# ProPrj_DRV8701.net
KiCad netlist of a schematic drawn in EasyEDA Pro
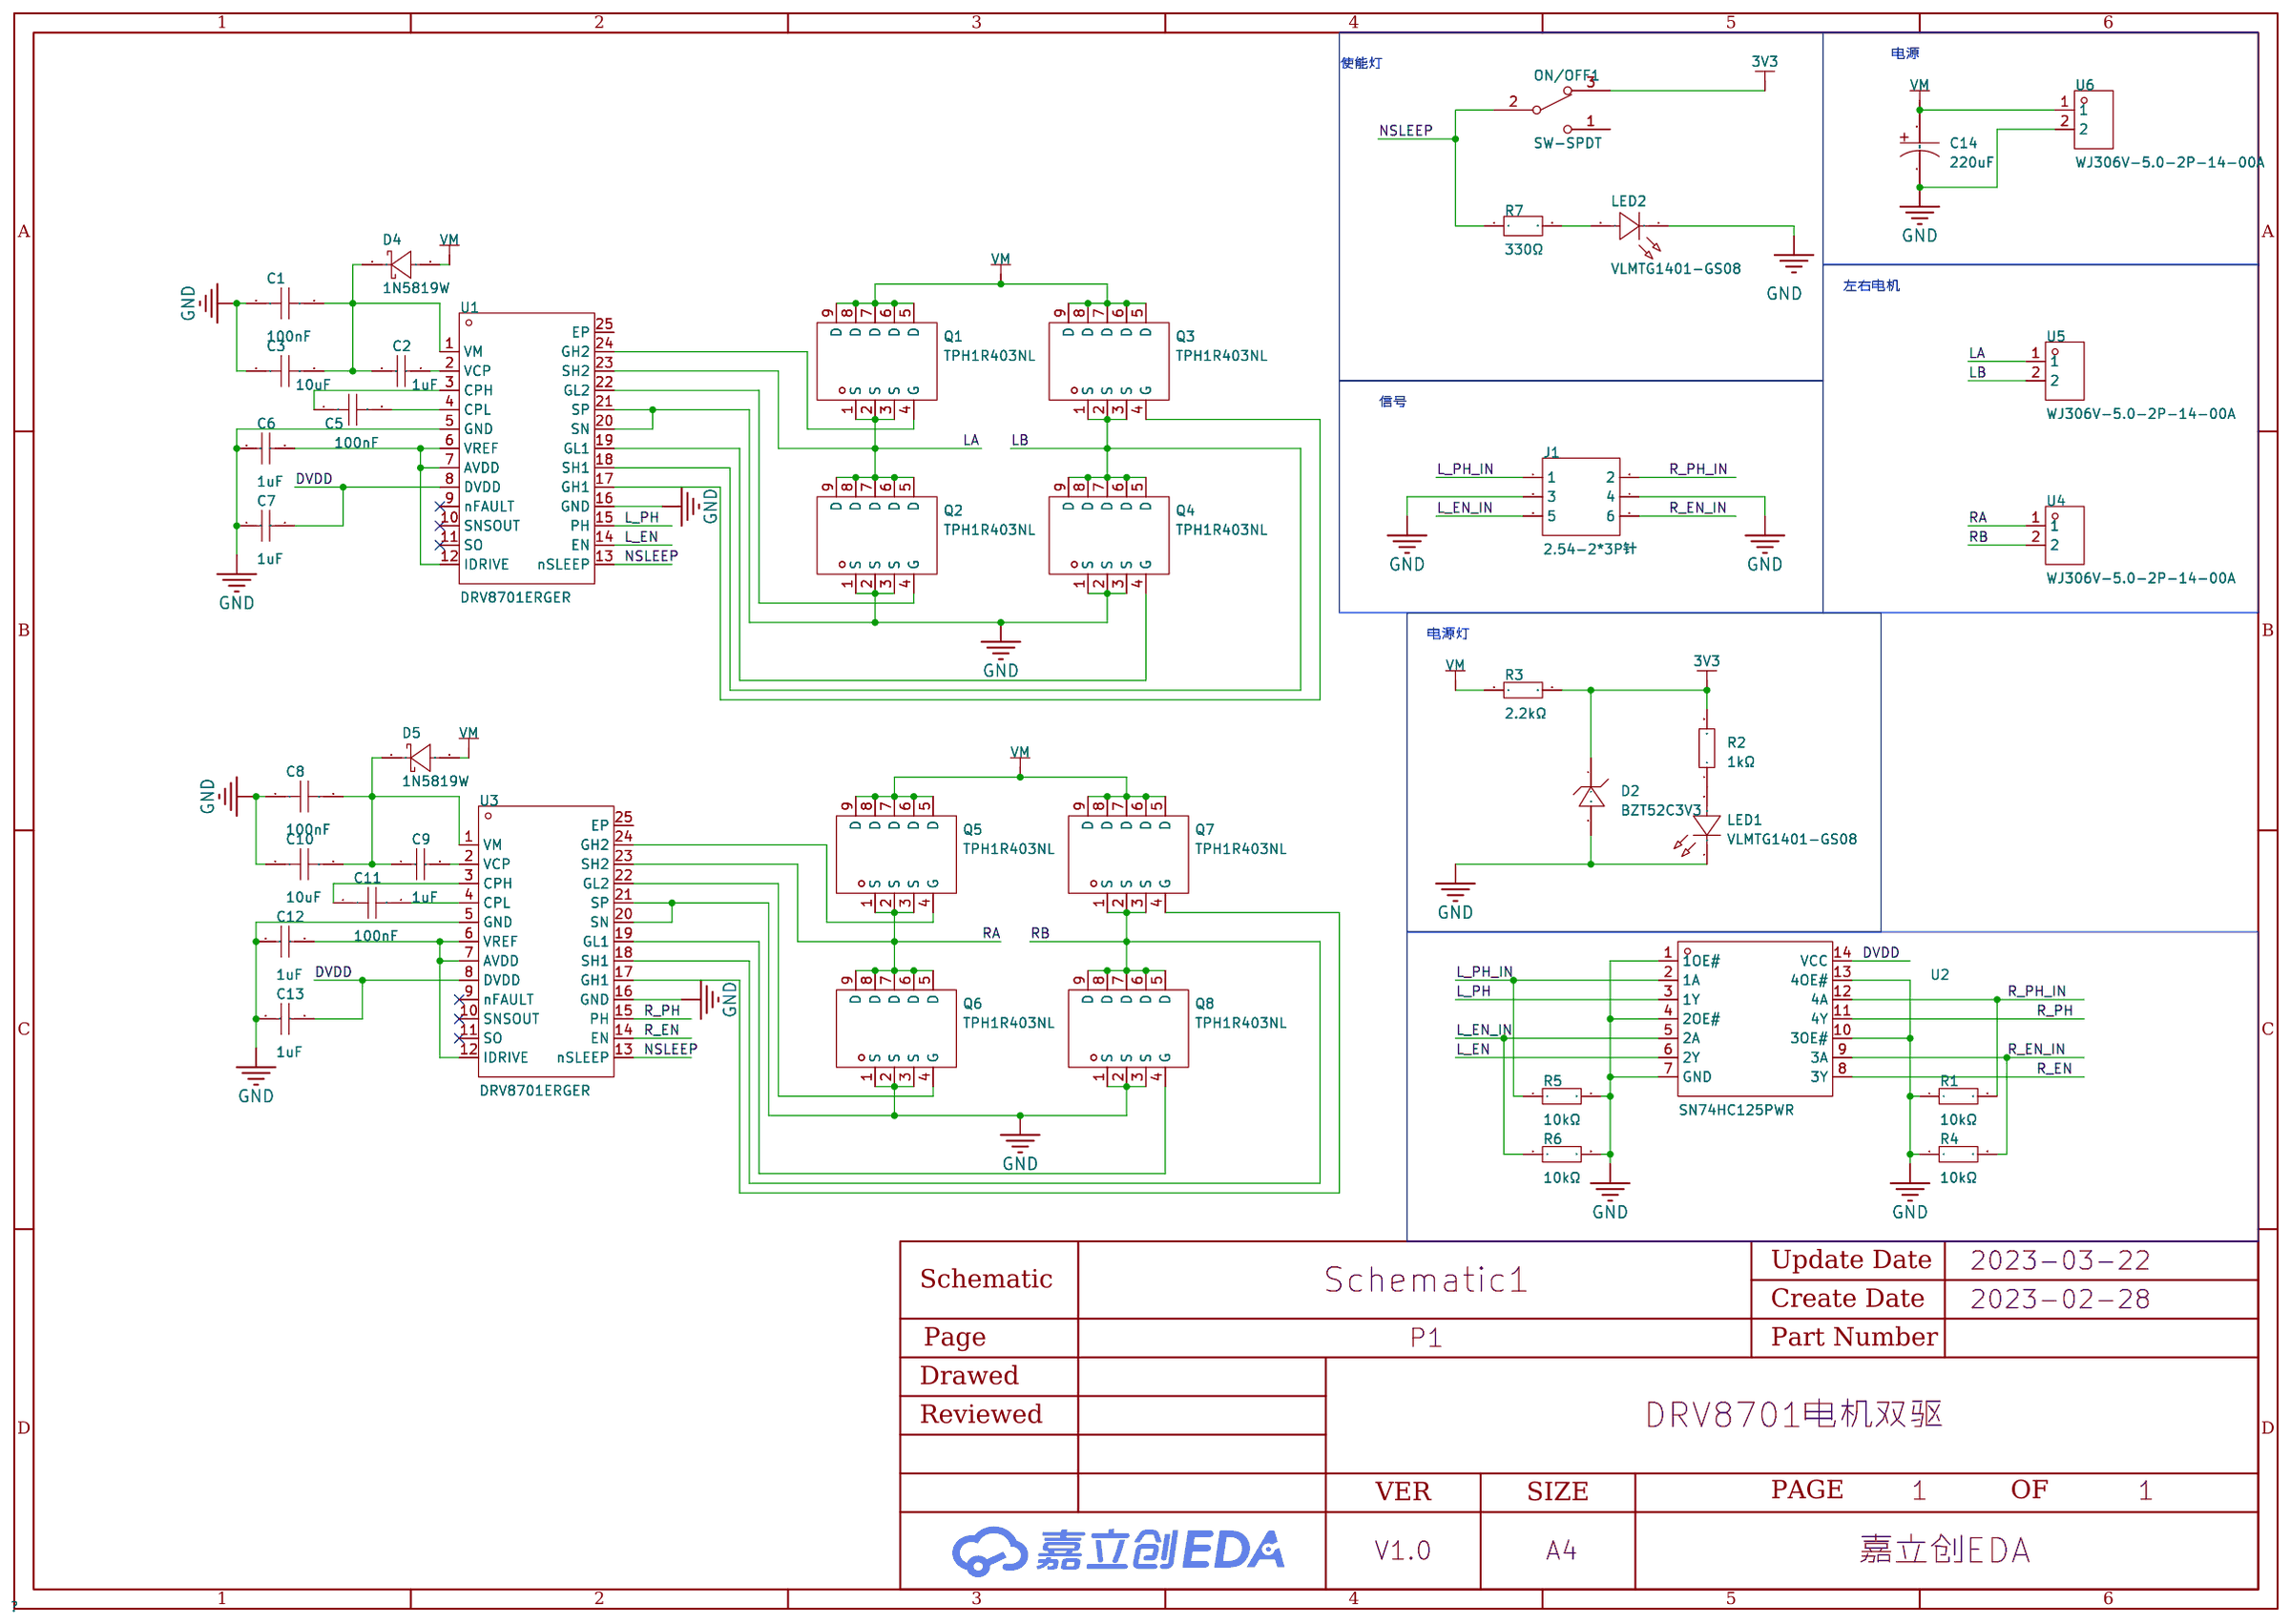
[diagram p0: schematic sheet]

(export (version "E")
  (design (tool "Eeschema 10.0.6"))
  (components
    (comp (ref "C1")
      (value "100nF")
      (footprint "easyedapro:C0603")
      (description "容值:100nF;精度:±10%;额定电压:50V;材质(温度系数):X7R;")
      (fields
        (field (name "Manufacturer Part") "CL10B104KB8NNNC")
        (field (name "Manufacturer") "SAMSUNG(三星)")
      )
      (libsource (lib "easyedapro") (part "CL10B104KB8NNNC"))
    )
    (comp (ref "C2")
      (value "1uF")
      (footprint "easyedapro:C0603")
      (description "容值:1uF;精度:±10%;额定电压:50V;材质(温度系数):X5R;")
      (fields
        (field (name "Manufacturer Part") "CL10A105KB8NNNC")
        (field (name "Manufacturer") "SAMSUNG(三星)")
      )
      (libsource (lib "easyedapro") (part "CL10A105KB8NNNC"))
    )
    (comp (ref "C3")
      (value "10uF")
      (footprint "easyedapro:C0805")
      (description "容值:10uF;精度:±10%;额定电压:50V;材质(温度系数):X5R;")
      (fields
        (field (name "Manufacturer Part") "CL21A106KBYQNNE")
        (field (name "Manufacturer") "SAMSUNG(三星)")
      )
      (libsource (lib "easyedapro") (part "CL21A106KBYQNNE"))
    )
    (comp (ref "C5")
      (value "100nF")
      (footprint "easyedapro:C0603")
      (description "容值:100nF;精度:±10%;额定电压:50V;材质(温度系数):X7R;")
      (fields
        (field (name "Manufacturer Part") "CL10B104KB8NNNC")
        (field (name "Manufacturer") "SAMSUNG(三星)")
      )
      (libsource (lib "easyedapro") (part "CL10B104KB8NNNC"))
    )
    (comp (ref "C6")
      (value "1uF")
      (footprint "easyedapro:C0603")
      (description "容值:1uF;精度:±10%;额定电压:50V;材质(温度系数):X5R;")
      (fields
        (field (name "Manufacturer Part") "CL10A105KB8NNNC")
        (field (name "Manufacturer") "SAMSUNG(三星)")
      )
      (libsource (lib "easyedapro") (part "CL10A105KB8NNNC"))
    )
    (comp (ref "C7")
      (value "1uF")
      (footprint "easyedapro:C0603")
      (description "容值:1uF;精度:±10%;额定电压:50V;材质(温度系数):X5R;")
      (fields
        (field (name "Manufacturer Part") "CL10A105KB8NNNC")
        (field (name "Manufacturer") "SAMSUNG(三星)")
      )
      (libsource (lib "easyedapro") (part "CL10A105KB8NNNC"))
    )
    (comp (ref "C8")
      (value "100nF")
      (footprint "easyedapro:C0603")
      (description "容值:100nF;精度:±10%;额定电压:50V;材质(温度系数):X7R;")
      (fields
        (field (name "Manufacturer Part") "CL10B104KB8NNNC")
        (field (name "Manufacturer") "SAMSUNG(三星)")
      )
      (libsource (lib "easyedapro") (part "CL10B104KB8NNNC"))
    )
    (comp (ref "C9")
      (value "1uF")
      (footprint "easyedapro:C0603")
      (description "容值:1uF;精度:±10%;额定电压:50V;材质(温度系数):X5R;")
      (fields
        (field (name "Manufacturer Part") "CL10A105KB8NNNC")
        (field (name "Manufacturer") "SAMSUNG(三星)")
      )
      (libsource (lib "easyedapro") (part "CL10A105KB8NNNC"))
    )
    (comp (ref "C10")
      (value "10uF")
      (footprint "easyedapro:C0805")
      (description "容值:10uF;精度:±10%;额定电压:50V;材质(温度系数):X5R;")
      (fields
        (field (name "Manufacturer Part") "CL21A106KBYQNNE")
        (field (name "Manufacturer") "SAMSUNG(三星)")
      )
      (libsource (lib "easyedapro") (part "CL21A106KBYQNNE"))
    )
    (comp (ref "C11")
      (value "100nF")
      (footprint "easyedapro:C0603")
      (description "容值:100nF;精度:±10%;额定电压:50V;材质(温度系数):X7R;")
      (fields
        (field (name "Manufacturer Part") "CL10B104KB8NNNC")
        (field (name "Manufacturer") "SAMSUNG(三星)")
      )
      (libsource (lib "easyedapro") (part "CL10B104KB8NNNC"))
    )
    (comp (ref "C12")
      (value "1uF")
      (footprint "easyedapro:C0603")
      (description "容值:1uF;精度:±10%;额定电压:50V;材质(温度系数):X5R;")
      (fields
        (field (name "Manufacturer Part") "CL10A105KB8NNNC")
        (field (name "Manufacturer") "SAMSUNG(三星)")
      )
      (libsource (lib "easyedapro") (part "CL10A105KB8NNNC"))
    )
    (comp (ref "C13")
      (value "1uF")
      (footprint "easyedapro:C0603")
      (description "容值:1uF;精度:±10%;额定电压:50V;材质(温度系数):X5R;")
      (fields
        (field (name "Manufacturer Part") "CL10A105KB8NNNC")
        (field (name "Manufacturer") "SAMSUNG(三星)")
      )
      (libsource (lib "easyedapro") (part "CL10A105KB8NNNC"))
    )
    (comp (ref "C14")
      (value "220uF")
      (footprint "easyedapro:CAP-SMD_BD8.0-L8.3-W8.3-FD")
      (fields (field (name "Manufacturer Part") "EEE1EA221UP") (field (name "Manufacturer") "PANASONIC(松下)"))
      (libsource (lib "easyedapro") (part "EEE1EA221UP"))
    )
    (comp (ref "D2")
      (value "BZT52C3V3")
      (footprint "easyedapro:SOD-123_L2.7-W1.6-LS3.7-RD-1")
      (description "二极管配置:-;稳压值(标称值):3.3V;稳压值(范围):3.3V~3.5V;功率:500mW;反向电流(Ir):5uA@1V;阻抗(Zzt):95Ω;")
      (fields (field (name "Manufacturer") "YONGYUTAI(永裕泰)"))
      (libsource (lib "easyedapro") (part "BZT52C3V3_C2891770"))
    )
    (comp (ref "D4")
      (value "1N5819W")
      (footprint "easyedapro:SOD-123_L2.7-W1.6-LS3.7-RD-1")
      (description "二极管配置:-;直流反向耐压(Vr):40V;平均整流电流(Io):1A;正向压降(Vf):900mV@3A;反向电流(Ir):1mA@40V;")
      (fields (field (name "Manufacturer") "TECH PUBLIC(台舟)"))
      (libsource (lib "easyedapro") (part "1N5819W_C2905650"))
    )
    (comp (ref "D5")
      (value "1N5819W")
      (footprint "easyedapro:SOD-123_L2.7-W1.6-LS3.7-RD-1")
      (description "二极管配置:-;直流反向耐压(Vr):40V;平均整流电流(Io):1A;正向压降(Vf):900mV@3A;反向电流(Ir):1mA@40V;")
      (fields (field (name "Manufacturer") "TECH PUBLIC(台舟)"))
      (libsource (lib "easyedapro") (part "1N5819W_C2905650"))
    )
    (comp (ref "J1")
      (value "2.54-2*3P针")
      (footprint "easyedapro:HDR-TH_6P-P2.54-V-M-R2-C3-S2.54-1")
      (fields (field (name "Manufacturer") "BOOMELE(博穆精密)"))
      (libsource (lib "easyedapro") (part "Header-Male-2.54_2x3"))
    )
    (comp (ref "LED1")
      (value "VLMTG1401-GS08")
      (footprint "easyedapro:LED0603-RD_GREEN")
      (description "照明颜色:-;色温 - CCT（K）:-;主波长/色坐标:-;正向电压（Vf）:-;")
      (fields (field (name "Manufacturer") "VISHAY(威世)"))
      (libsource (lib "easyedapro") (part "VLMTG1401-GS08"))
    )
    (comp (ref "LED2")
      (value "VLMTG1401-GS08")
      (footprint "easyedapro:LED0603-RD_GREEN")
      (description "照明颜色:-;色温 - CCT（K）:-;主波长/色坐标:-;正向电压（Vf）:-;")
      (fields (field (name "Manufacturer") "VISHAY(威世)"))
      (libsource (lib "easyedapro") (part "VLMTG1401-GS08"))
    )
    (comp (ref "ON/OFF1")
      (value "SW-SPDT")
      (footprint "easyedapro:SS12D10")
      (libsource (lib "easyedapro") (part "SW-SPDT"))
    )
    (comp (ref "Q1")
      (value "TPH1R403NL")
      (footprint "easyedapro:DSOP-8_L5.0-W5.0-P1.27-LS6.0-BL-EP")
      (fields (field (name "Manufacturer") "TOSHIBA(东芝)"))
      (libsource (lib "easyedapro") (part "TPH1R403NL"))
    )
    (comp (ref "Q2")
      (value "TPH1R403NL")
      (footprint "easyedapro:DSOP-8_L5.0-W5.0-P1.27-LS6.0-BL-EP")
      (fields (field (name "Manufacturer") "TOSHIBA(东芝)"))
      (libsource (lib "easyedapro") (part "TPH1R403NL"))
    )
    (comp (ref "Q3")
      (value "TPH1R403NL")
      (footprint "easyedapro:DSOP-8_L5.0-W5.0-P1.27-LS6.0-BL-EP")
      (fields (field (name "Manufacturer") "TOSHIBA(东芝)"))
      (libsource (lib "easyedapro") (part "TPH1R403NL"))
    )
    (comp (ref "Q4")
      (value "TPH1R403NL")
      (footprint "easyedapro:DSOP-8_L5.0-W5.0-P1.27-LS6.0-BL-EP")
      (fields (field (name "Manufacturer") "TOSHIBA(东芝)"))
      (libsource (lib "easyedapro") (part "TPH1R403NL"))
    )
    (comp (ref "Q5")
      (value "TPH1R403NL")
      (footprint "easyedapro:DSOP-8_L5.0-W5.0-P1.27-LS6.0-BL-EP")
      (fields (field (name "Manufacturer") "TOSHIBA(东芝)"))
      (libsource (lib "easyedapro") (part "TPH1R403NL"))
    )
    (comp (ref "Q6")
      (value "TPH1R403NL")
      (footprint "easyedapro:DSOP-8_L5.0-W5.0-P1.27-LS6.0-BL-EP")
      (fields (field (name "Manufacturer") "TOSHIBA(东芝)"))
      (libsource (lib "easyedapro") (part "TPH1R403NL"))
    )
    (comp (ref "Q7")
      (value "TPH1R403NL")
      (footprint "easyedapro:DSOP-8_L5.0-W5.0-P1.27-LS6.0-BL-EP")
      (fields (field (name "Manufacturer") "TOSHIBA(东芝)"))
      (libsource (lib "easyedapro") (part "TPH1R403NL"))
    )
    (comp (ref "Q8")
      (value "TPH1R403NL")
      (footprint "easyedapro:DSOP-8_L5.0-W5.0-P1.27-LS6.0-BL-EP")
      (fields (field (name "Manufacturer") "TOSHIBA(东芝)"))
      (libsource (lib "easyedapro") (part "TPH1R403NL"))
    )
    (comp (ref "R1")
      (value "10kΩ")
      (footprint "easyedapro:R0603")
      (description "电阻类型:厚膜电阻;阻值:10kΩ;精度:±1%;功率:100mW;温度系数:±100ppm/°C;最大工作电压:75V;工作温度范围:-55°C~+155°C;")
      (fields
        (field (name "Manufacturer Part") "0603WAF1002T5E")
        (field (name "Manufacturer") "UNI-ROYAL(厚声)")
      )
      (libsource (lib "easyedapro") (part "0603WAF1002T5E"))
    )
    (comp (ref "R2")
      (value "1kΩ")
      (footprint "easyedapro:R0603")
      (description "阻值:1kΩ;精度:±1%;功率:100mW;温度系数:±100ppm/°C;最大工作电压:75V;工作温度范围:-55°C~+155°C;")
      (fields (field (name "Manufacturer Part") "RC0603FR-071KL") (field (name "Manufacturer") "YAGEO(国巨)"))
      (libsource (lib "easyedapro") (part "RC0603FR-071KL"))
    )
    (comp (ref "R3")
      (value "2.2kΩ")
      (footprint "easyedapro:R0603")
      (description "电阻类型:薄膜电阻;阻值:2.2kΩ;精度:±0.1%;功率:100mW;温度系数:±25ppm/K;最大工作电压:75V;工作温度范围:-55°C~+155°C;")
      (fields (field (name "Manufacturer Part") "ERA3AEB222V") (field (name "Manufacturer") "PANASONIC(松下)"))
      (libsource (lib "easyedapro") (part "ERA3AEB222V"))
    )
    (comp (ref "R4")
      (value "10kΩ")
      (footprint "easyedapro:R0603")
      (description "电阻类型:厚膜电阻;阻值:10kΩ;精度:±1%;功率:100mW;温度系数:±100ppm/°C;最大工作电压:75V;工作温度范围:-55°C~+155°C;")
      (fields
        (field (name "Manufacturer Part") "0603WAF1002T5E")
        (field (name "Manufacturer") "UNI-ROYAL(厚声)")
      )
      (libsource (lib "easyedapro") (part "0603WAF1002T5E"))
    )
    (comp (ref "R5")
      (value "10kΩ")
      (footprint "easyedapro:R0603")
      (description "电阻类型:厚膜电阻;阻值:10kΩ;精度:±1%;功率:100mW;温度系数:±100ppm/°C;最大工作电压:75V;工作温度范围:-55°C~+155°C;")
      (fields
        (field (name "Manufacturer Part") "0603WAF1002T5E")
        (field (name "Manufacturer") "UNI-ROYAL(厚声)")
      )
      (libsource (lib "easyedapro") (part "0603WAF1002T5E"))
    )
    (comp (ref "R6")
      (value "10kΩ")
      (footprint "easyedapro:R0603")
      (description "电阻类型:厚膜电阻;阻值:10kΩ;精度:±1%;功率:100mW;温度系数:±100ppm/°C;最大工作电压:75V;工作温度范围:-55°C~+155°C;")
      (fields
        (field (name "Manufacturer Part") "0603WAF1002T5E")
        (field (name "Manufacturer") "UNI-ROYAL(厚声)")
      )
      (libsource (lib "easyedapro") (part "0603WAF1002T5E"))
    )
    (comp (ref "R7")
      (value "330Ω")
      (footprint "easyedapro:R0603")
      (description "电阻类型:厚膜电阻;阻值:330Ω;精度:±5%;功率:100mW;温度系数:±200ppm/°C;最大工作电压:-;工作温度范围:-55°C~+155°C;")
      (fields (field (name "Manufacturer Part") "ERJ3GEYJ331V") (field (name "Manufacturer") "PANASONIC(松下)"))
      (libsource (lib "easyedapro") (part "ERJ3GEYJ331V"))
    )
    (comp (ref "U1")
      (value "DRV8701ERGER")
      (footprint "easyedapro:VQFN-24_L4.0-W4.0-P0.50-BL-EP2.5")
      (description "DRV8701 DRV8701 H 桥栅极驱动器")
      (fields (field (name "Manufacturer") "TI(德州仪器)"))
      (libsource (lib "easyedapro") (part "DRV8701ERGER"))
    )
    (comp (ref "U2")
      (value "SN74HC125PWR")
      (footprint "easyedapro:TSSOP-14_L5.0-W4.4-P0.65-LS6.5-BL")
      (description "类型:缓冲器，非反相;电源电压:2V~6V;输入类型:-;输出类型:三态;低电平输出电流(IOL):7.8mA;高电平输出电流(IOH):7.8mA;工作温度:-40°C~+85°C;")
      (fields (field (name "Manufacturer") "TI(德州仪器)"))
      (libsource (lib "easyedapro") (part "SN74HC125PWR"))
    )
    (comp (ref "U3")
      (value "DRV8701ERGER")
      (footprint "easyedapro:VQFN-24_L4.0-W4.0-P0.50-BL-EP2.5")
      (description "DRV8701 DRV8701 H 桥栅极驱动器")
      (fields (field (name "Manufacturer") "TI(德州仪器)"))
      (libsource (lib "easyedapro") (part "DRV8701ERGER"))
    )
    (comp (ref "U4")
      (value "WJ306V-5.0-2P-14-00A")
      (footprint "easyedapro:CONN-TH_2P-P5.00_L7.6-W10.0")
      (fields (field (name "Manufacturer") "KANGNEX(康奈克斯电气)"))
      (libsource (lib "easyedapro") (part "WJ306V-5.0-2P-14-00A"))
    )
    (comp (ref "U5")
      (value "WJ306V-5.0-2P-14-00A")
      (footprint "easyedapro:CONN-TH_2P-P5.00_L7.6-W10.0")
      (fields (field (name "Manufacturer") "KANGNEX(康奈克斯电气)"))
      (libsource (lib "easyedapro") (part "WJ306V-5.0-2P-14-00A"))
    )
    (comp (ref "U6")
      (value "WJ306V-5.0-2P-14-00A")
      (footprint "easyedapro:CONN-TH_2P-P5.00_L7.6-W10.0")
      (fields (field (name "Manufacturer") "KANGNEX(康奈克斯电气)"))
      (libsource (lib "easyedapro") (part "WJ306V-5.0-2P-14-00A"))
    )
  )
  (nets
    (net (code "1") (name "/DVDD") (class "Default")
      (node (ref "C13") (pin "2") (pinfunction "2_2") (pintype "input"))
      (node (ref "C7") (pin "2") (pinfunction "2_2") (pintype "input"))
      (node (ref "U1") (pin "8") (pinfunction "DVDD_8") (pintype "input"))
      (node (ref "U2") (pin "14") (pinfunction "VCC_14") (pintype "input"))
      (node (ref "U3") (pin "8") (pinfunction "DVDD_8") (pintype "input"))
    )
    (net (code "2") (name "/LA") (class "Default")
      (node (ref "Q1") (pin "1") (pinfunction "S_1") (pintype "input"))
      (node (ref "Q1") (pin "2") (pinfunction "S_2") (pintype "input"))
      (node (ref "Q1") (pin "3") (pinfunction "S_3") (pintype "input"))
      (node (ref "Q2") (pin "5") (pinfunction "D_5") (pintype "input"))
      (node (ref "Q2") (pin "6") (pinfunction "D_6") (pintype "input"))
      (node (ref "Q2") (pin "7") (pinfunction "D_7") (pintype "input"))
      (node (ref "Q2") (pin "8") (pinfunction "D_8") (pintype "input"))
      (node (ref "Q2") (pin "9") (pinfunction "D_9") (pintype "input"))
      (node (ref "U1") (pin "23") (pinfunction "SH2_23") (pintype "input"))
      (node (ref "U5") (pin "1") (pinfunction "1_1") (pintype "input"))
    )
    (net (code "3") (name "/LB") (class "Default")
      (node (ref "Q3") (pin "1") (pinfunction "S_1") (pintype "input"))
      (node (ref "Q3") (pin "2") (pinfunction "S_2") (pintype "input"))
      (node (ref "Q3") (pin "3") (pinfunction "S_3") (pintype "input"))
      (node (ref "Q4") (pin "5") (pinfunction "D_5") (pintype "input"))
      (node (ref "Q4") (pin "6") (pinfunction "D_6") (pintype "input"))
      (node (ref "Q4") (pin "7") (pinfunction "D_7") (pintype "input"))
      (node (ref "Q4") (pin "8") (pinfunction "D_8") (pintype "input"))
      (node (ref "Q4") (pin "9") (pinfunction "D_9") (pintype "input"))
      (node (ref "U1") (pin "18") (pinfunction "SH1_18") (pintype "input"))
      (node (ref "U5") (pin "2") (pinfunction "2_2") (pintype "input"))
    )
    (net (code "4") (name "/L_EN") (class "Default")
      (node (ref "U1") (pin "14") (pinfunction "EN_14") (pintype "input"))
      (node (ref "U2") (pin "6") (pinfunction "2Y_6") (pintype "input"))
    )
    (net (code "5") (name "/L_EN_IN") (class "Default")
      (node (ref "J1") (pin "5") (pinfunction "5_5") (pintype "input"))
      (node (ref "R6") (pin "1") (pinfunction "1_1") (pintype "input"))
      (node (ref "U2") (pin "5") (pinfunction "2A_5") (pintype "input"))
    )
    (net (code "6") (name "/L_PH") (class "Default")
      (node (ref "U1") (pin "15") (pinfunction "PH_15") (pintype "input"))
      (node (ref "U2") (pin "3") (pinfunction "1Y_3") (pintype "input"))
    )
    (net (code "7") (name "/L_PH_IN") (class "Default")
      (node (ref "J1") (pin "1") (pinfunction "1_1") (pintype "input"))
      (node (ref "R5") (pin "1") (pinfunction "1_1") (pintype "input"))
      (node (ref "U2") (pin "2") (pinfunction "1A_2") (pintype "input"))
    )
    (net (code "8") (name "/NSLEEP") (class "Default")
      (node (ref "ON/OFF1") (pin "2") (pintype "input"))
      (node (ref "R7") (pin "1") (pinfunction "1_1") (pintype "input"))
      (node (ref "U1") (pin "13") (pinfunction "nSLEEP_13") (pintype "input"))
      (node (ref "U3") (pin "13") (pinfunction "nSLEEP_13") (pintype "input"))
    )
    (net (code "9") (name "/RA") (class "Default")
      (node (ref "Q5") (pin "1") (pinfunction "S_1") (pintype "input"))
      (node (ref "Q5") (pin "2") (pinfunction "S_2") (pintype "input"))
      (node (ref "Q5") (pin "3") (pinfunction "S_3") (pintype "input"))
      (node (ref "Q6") (pin "5") (pinfunction "D_5") (pintype "input"))
      (node (ref "Q6") (pin "6") (pinfunction "D_6") (pintype "input"))
      (node (ref "Q6") (pin "7") (pinfunction "D_7") (pintype "input"))
      (node (ref "Q6") (pin "8") (pinfunction "D_8") (pintype "input"))
      (node (ref "Q6") (pin "9") (pinfunction "D_9") (pintype "input"))
      (node (ref "U3") (pin "23") (pinfunction "SH2_23") (pintype "input"))
      (node (ref "U4") (pin "1") (pinfunction "1_1") (pintype "input"))
    )
    (net (code "10") (name "/RB") (class "Default")
      (node (ref "Q7") (pin "1") (pinfunction "S_1") (pintype "input"))
      (node (ref "Q7") (pin "2") (pinfunction "S_2") (pintype "input"))
      (node (ref "Q7") (pin "3") (pinfunction "S_3") (pintype "input"))
      (node (ref "Q8") (pin "5") (pinfunction "D_5") (pintype "input"))
      (node (ref "Q8") (pin "6") (pinfunction "D_6") (pintype "input"))
      (node (ref "Q8") (pin "7") (pinfunction "D_7") (pintype "input"))
      (node (ref "Q8") (pin "8") (pinfunction "D_8") (pintype "input"))
      (node (ref "Q8") (pin "9") (pinfunction "D_9") (pintype "input"))
      (node (ref "U3") (pin "18") (pinfunction "SH1_18") (pintype "input"))
      (node (ref "U4") (pin "2") (pinfunction "2_2") (pintype "input"))
    )
    (net (code "11") (name "/R_EN") (class "Default")
      (node (ref "U2") (pin "8") (pinfunction "3Y_8") (pintype "input"))
      (node (ref "U3") (pin "14") (pinfunction "EN_14") (pintype "input"))
    )
    (net (code "12") (name "/R_EN_IN") (class "Default")
      (node (ref "J1") (pin "6") (pinfunction "6_6") (pintype "input"))
      (node (ref "R4") (pin "2") (pinfunction "2_2") (pintype "input"))
      (node (ref "U2") (pin "9") (pinfunction "3A_9") (pintype "input"))
    )
    (net (code "13") (name "/R_PH") (class "Default")
      (node (ref "U2") (pin "11") (pinfunction "4Y_11") (pintype "input"))
      (node (ref "U3") (pin "15") (pinfunction "PH_15") (pintype "input"))
    )
    (net (code "14") (name "/R_PH_IN") (class "Default")
      (node (ref "J1") (pin "2") (pinfunction "2_2") (pintype "input"))
      (node (ref "R1") (pin "2") (pinfunction "2_2") (pintype "input"))
      (node (ref "U2") (pin "12") (pinfunction "4A_12") (pintype "input"))
    )
    (net (code "15") (name "3V3") (class "Default")
      (node (ref "D2") (pin "1") (pinfunction "1_1") (pintype "input"))
      (node (ref "ON/OFF1") (pin "3") (pintype "input"))
      (node (ref "R2") (pin "2") (pinfunction "2_2") (pintype "input"))
      (node (ref "R3") (pin "2") (pinfunction "2_2") (pintype "input"))
    )
    (net (code "16") (name "GND") (class "Default")
      (node (ref "C1") (pin "1") (pinfunction "1_1") (pintype "input"))
      (node (ref "C10") (pin "1") (pinfunction "1_1") (pintype "input"))
      (node (ref "C12") (pin "1") (pinfunction "1_1") (pintype "input"))
      (node (ref "C13") (pin "1") (pinfunction "1_1") (pintype "input"))
      (node (ref "C14") (pin "2") (pinfunction "2_2") (pintype "input"))
      (node (ref "C3") (pin "1") (pinfunction "1_1") (pintype "input"))
      (node (ref "C6") (pin "1") (pinfunction "1_1") (pintype "input"))
      (node (ref "C7") (pin "1") (pinfunction "1_1") (pintype "input"))
      (node (ref "C8") (pin "1") (pinfunction "1_1") (pintype "input"))
      (node (ref "D2") (pin "2") (pinfunction "2_2") (pintype "input"))
      (node (ref "J1") (pin "3") (pinfunction "3_3") (pintype "input"))
      (node (ref "J1") (pin "4") (pinfunction "4_4") (pintype "input"))
      (node (ref "LED1") (pin "1") (pinfunction "K_1") (pintype "input"))
      (node (ref "LED2") (pin "1") (pinfunction "K_1") (pintype "input"))
      (node (ref "Q2") (pin "1") (pinfunction "S_1") (pintype "input"))
      (node (ref "Q2") (pin "2") (pinfunction "S_2") (pintype "input"))
      (node (ref "Q2") (pin "3") (pinfunction "S_3") (pintype "input"))
      (node (ref "Q4") (pin "1") (pinfunction "S_1") (pintype "input"))
      (node (ref "Q4") (pin "2") (pinfunction "S_2") (pintype "input"))
      (node (ref "Q4") (pin "3") (pinfunction "S_3") (pintype "input"))
      (node (ref "Q6") (pin "1") (pinfunction "S_1") (pintype "input"))
      (node (ref "Q6") (pin "2") (pinfunction "S_2") (pintype "input"))
      (node (ref "Q6") (pin "3") (pinfunction "S_3") (pintype "input"))
      (node (ref "Q8") (pin "1") (pinfunction "S_1") (pintype "input"))
      (node (ref "Q8") (pin "2") (pinfunction "S_2") (pintype "input"))
      (node (ref "Q8") (pin "3") (pinfunction "S_3") (pintype "input"))
      (node (ref "R1") (pin "1") (pinfunction "1_1") (pintype "input"))
      (node (ref "R4") (pin "1") (pinfunction "1_1") (pintype "input"))
      (node (ref "R5") (pin "2") (pinfunction "2_2") (pintype "input"))
      (node (ref "R6") (pin "2") (pinfunction "2_2") (pintype "input"))
      (node (ref "U1") (pin "16") (pinfunction "GND_16") (pintype "input"))
      (node (ref "U1") (pin "20") (pinfunction "SN_20") (pintype "input"))
      (node (ref "U1") (pin "21") (pinfunction "SP_21") (pintype "input"))
      (node (ref "U1") (pin "5") (pinfunction "GND_5") (pintype "input"))
      (node (ref "U2") (pin "1") (pinfunction "1OE#_1") (pintype "input"))
      (node (ref "U2") (pin "10") (pinfunction "3OE#_10") (pintype "input"))
      (node (ref "U2") (pin "13") (pinfunction "4OE#_13") (pintype "input"))
      (node (ref "U2") (pin "4") (pinfunction "2OE#_4") (pintype "input"))
      (node (ref "U2") (pin "7") (pinfunction "GND_7") (pintype "input"))
      (node (ref "U3") (pin "16") (pinfunction "GND_16") (pintype "input"))
      (node (ref "U3") (pin "20") (pinfunction "SN_20") (pintype "input"))
      (node (ref "U3") (pin "21") (pinfunction "SP_21") (pintype "input"))
      (node (ref "U3") (pin "5") (pinfunction "GND_5") (pintype "input"))
      (node (ref "U6") (pin "2") (pinfunction "2_2") (pintype "input"))
    )
    (net (code "17") (name "Net-(D4-K)") (class "Default")
      (node (ref "C1") (pin "2") (pinfunction "2_2") (pintype "input"))
      (node (ref "C2") (pin "1") (pinfunction "1_1") (pintype "input"))
      (node (ref "C3") (pin "2") (pinfunction "2_2") (pintype "input"))
      (node (ref "D4") (pin "1") (pinfunction "K_1") (pintype "input"))
      (node (ref "U1") (pin "1") (pinfunction "VM_1") (pintype "input"))
    )
    (net (code "18") (name "Net-(D5-K)") (class "Default")
      (node (ref "C10") (pin "2") (pinfunction "2_2") (pintype "input"))
      (node (ref "C8") (pin "2") (pinfunction "2_2") (pintype "input"))
      (node (ref "C9") (pin "1") (pinfunction "1_1") (pintype "input"))
      (node (ref "D5") (pin "1") (pinfunction "K_1") (pintype "input"))
      (node (ref "U3") (pin "1") (pinfunction "VM_1") (pintype "input"))
    )
    (net (code "19") (name "Net-(LED1-A)") (class "Default")
      (node (ref "LED1") (pin "2") (pinfunction "A_2") (pintype "input"))
      (node (ref "R2") (pin "1") (pinfunction "1_1") (pintype "input"))
    )
    (net (code "20") (name "Net-(LED2-A)") (class "Default")
      (node (ref "LED2") (pin "2") (pinfunction "A_2") (pintype "input"))
      (node (ref "R7") (pin "2") (pinfunction "2_2") (pintype "input"))
    )
    (net (code "21") (name "Net-(Q1-G)") (class "Default")
      (node (ref "Q1") (pin "4") (pinfunction "G_4") (pintype "input"))
      (node (ref "U1") (pin "24") (pinfunction "GH2_24") (pintype "input"))
    )
    (net (code "22") (name "Net-(Q2-G)") (class "Default")
      (node (ref "Q2") (pin "4") (pinfunction "G_4") (pintype "input"))
      (node (ref "U1") (pin "22") (pinfunction "GL2_22") (pintype "input"))
    )
    (net (code "23") (name "Net-(Q3-G)") (class "Default")
      (node (ref "Q3") (pin "4") (pinfunction "G_4") (pintype "input"))
      (node (ref "U1") (pin "17") (pinfunction "GH1_17") (pintype "input"))
    )
    (net (code "24") (name "Net-(Q4-G)") (class "Default")
      (node (ref "Q4") (pin "4") (pinfunction "G_4") (pintype "input"))
      (node (ref "U1") (pin "19") (pinfunction "GL1_19") (pintype "input"))
    )
    (net (code "25") (name "Net-(Q5-G)") (class "Default")
      (node (ref "Q5") (pin "4") (pinfunction "G_4") (pintype "input"))
      (node (ref "U3") (pin "24") (pinfunction "GH2_24") (pintype "input"))
    )
    (net (code "26") (name "Net-(Q6-G)") (class "Default")
      (node (ref "Q6") (pin "4") (pinfunction "G_4") (pintype "input"))
      (node (ref "U3") (pin "22") (pinfunction "GL2_22") (pintype "input"))
    )
    (net (code "27") (name "Net-(Q7-G)") (class "Default")
      (node (ref "Q7") (pin "4") (pinfunction "G_4") (pintype "input"))
      (node (ref "U3") (pin "17") (pinfunction "GH1_17") (pintype "input"))
    )
    (net (code "28") (name "Net-(Q8-G)") (class "Default")
      (node (ref "Q8") (pin "4") (pinfunction "G_4") (pintype "input"))
      (node (ref "U3") (pin "19") (pinfunction "GL1_19") (pintype "input"))
    )
    (net (code "29") (name "Net-(U1-AVDD)") (class "Default")
      (node (ref "C6") (pin "2") (pinfunction "2_2") (pintype "input"))
      (node (ref "U1") (pin "12") (pinfunction "IDRIVE_12") (pintype "input"))
      (node (ref "U1") (pin "6") (pinfunction "VREF_6") (pintype "input"))
      (node (ref "U1") (pin "7") (pinfunction "AVDD_7") (pintype "input"))
    )
    (net (code "30") (name "Net-(U1-CPH)") (class "Default")
      (node (ref "C5") (pin "1") (pinfunction "1_1") (pintype "input"))
      (node (ref "U1") (pin "3") (pinfunction "CPH_3") (pintype "input"))
    )
    (net (code "31") (name "Net-(U1-CPL)") (class "Default")
      (node (ref "C5") (pin "2") (pinfunction "2_2") (pintype "input"))
      (node (ref "U1") (pin "4") (pinfunction "CPL_4") (pintype "input"))
    )
    (net (code "32") (name "Net-(U1-VCP)") (class "Default")
      (node (ref "C2") (pin "2") (pinfunction "2_2") (pintype "input"))
      (node (ref "U1") (pin "2") (pinfunction "VCP_2") (pintype "input"))
    )
    (net (code "33") (name "Net-(U3-AVDD)") (class "Default")
      (node (ref "C12") (pin "2") (pinfunction "2_2") (pintype "input"))
      (node (ref "U3") (pin "12") (pinfunction "IDRIVE_12") (pintype "input"))
      (node (ref "U3") (pin "6") (pinfunction "VREF_6") (pintype "input"))
      (node (ref "U3") (pin "7") (pinfunction "AVDD_7") (pintype "input"))
    )
    (net (code "34") (name "Net-(U3-CPH)") (class "Default")
      (node (ref "C11") (pin "1") (pinfunction "1_1") (pintype "input"))
      (node (ref "U3") (pin "3") (pinfunction "CPH_3") (pintype "input"))
    )
    (net (code "35") (name "Net-(U3-CPL)") (class "Default")
      (node (ref "C11") (pin "2") (pinfunction "2_2") (pintype "input"))
      (node (ref "U3") (pin "4") (pinfunction "CPL_4") (pintype "input"))
    )
    (net (code "36") (name "Net-(U3-VCP)") (class "Default")
      (node (ref "C9") (pin "2") (pinfunction "2_2") (pintype "input"))
      (node (ref "U3") (pin "2") (pinfunction "VCP_2") (pintype "input"))
    )
    (net (code "37") (name "VM") (class "Default")
      (node (ref "C14") (pin "1") (pinfunction "1_1") (pintype "input"))
      (node (ref "D4") (pin "2") (pinfunction "A_2") (pintype "input"))
      (node (ref "D5") (pin "2") (pinfunction "A_2") (pintype "input"))
      (node (ref "Q1") (pin "5") (pinfunction "D_5") (pintype "input"))
      (node (ref "Q1") (pin "6") (pinfunction "D_6") (pintype "input"))
      (node (ref "Q1") (pin "7") (pinfunction "D_7") (pintype "input"))
      (node (ref "Q1") (pin "8") (pinfunction "D_8") (pintype "input"))
      (node (ref "Q1") (pin "9") (pinfunction "D_9") (pintype "input"))
      (node (ref "Q3") (pin "5") (pinfunction "D_5") (pintype "input"))
      (node (ref "Q3") (pin "6") (pinfunction "D_6") (pintype "input"))
      (node (ref "Q3") (pin "7") (pinfunction "D_7") (pintype "input"))
      (node (ref "Q3") (pin "8") (pinfunction "D_8") (pintype "input"))
      (node (ref "Q3") (pin "9") (pinfunction "D_9") (pintype "input"))
      (node (ref "Q5") (pin "5") (pinfunction "D_5") (pintype "input"))
      (node (ref "Q5") (pin "6") (pinfunction "D_6") (pintype "input"))
      (node (ref "Q5") (pin "7") (pinfunction "D_7") (pintype "input"))
      (node (ref "Q5") (pin "8") (pinfunction "D_8") (pintype "input"))
      (node (ref "Q5") (pin "9") (pinfunction "D_9") (pintype "input"))
      (node (ref "Q7") (pin "5") (pinfunction "D_5") (pintype "input"))
      (node (ref "Q7") (pin "6") (pinfunction "D_6") (pintype "input"))
      (node (ref "Q7") (pin "7") (pinfunction "D_7") (pintype "input"))
      (node (ref "Q7") (pin "8") (pinfunction "D_8") (pintype "input"))
      (node (ref "Q7") (pin "9") (pinfunction "D_9") (pintype "input"))
      (node (ref "R3") (pin "1") (pinfunction "1_1") (pintype "input"))
      (node (ref "U6") (pin "1") (pinfunction "1_1") (pintype "input"))
    )
    (net (code "38") (name "unconnected-(ON/OFF1-Pad1)") (class "Default")
      (node (ref "ON/OFF1") (pin "1") (pintype "input"))
    )
    (net (code "39") (name "unconnected-(U1-EP-Pad25)") (class "Default")
      (node (ref "U1") (pin "25") (pinfunction "EP_25") (pintype "input"))
    )
    (net (code "40") (name "unconnected-(U1-SNSOUT-Pad10)") (class "Default")
      (node (ref "U1") (pin "10") (pinfunction "SNSOUT_10") (pintype "input+no_connect"))
    )
    (net (code "41") (name "unconnected-(U1-SO-Pad11)") (class "Default")
      (node (ref "U1") (pin "11") (pinfunction "SO_11") (pintype "input+no_connect"))
    )
    (net (code "42") (name "unconnected-(U1-nFAULT-Pad9)") (class "Default")
      (node (ref "U1") (pin "9") (pinfunction "nFAULT_9") (pintype "input+no_connect"))
    )
    (net (code "43") (name "unconnected-(U3-EP-Pad25)") (class "Default")
      (node (ref "U3") (pin "25") (pinfunction "EP_25") (pintype "input"))
    )
    (net (code "44") (name "unconnected-(U3-SNSOUT-Pad10)") (class "Default")
      (node (ref "U3") (pin "10") (pinfunction "SNSOUT_10") (pintype "input+no_connect"))
    )
    (net (code "45") (name "unconnected-(U3-SO-Pad11)") (class "Default")
      (node (ref "U3") (pin "11") (pinfunction "SO_11") (pintype "input+no_connect"))
    )
    (net (code "46") (name "unconnected-(U3-nFAULT-Pad9)") (class "Default")
      (node (ref "U3") (pin "9") (pinfunction "nFAULT_9") (pintype "input+no_connect"))
    )
  )
)
